# CODEC.net
KiCad netlist of a schematic drawn in Altium Designer
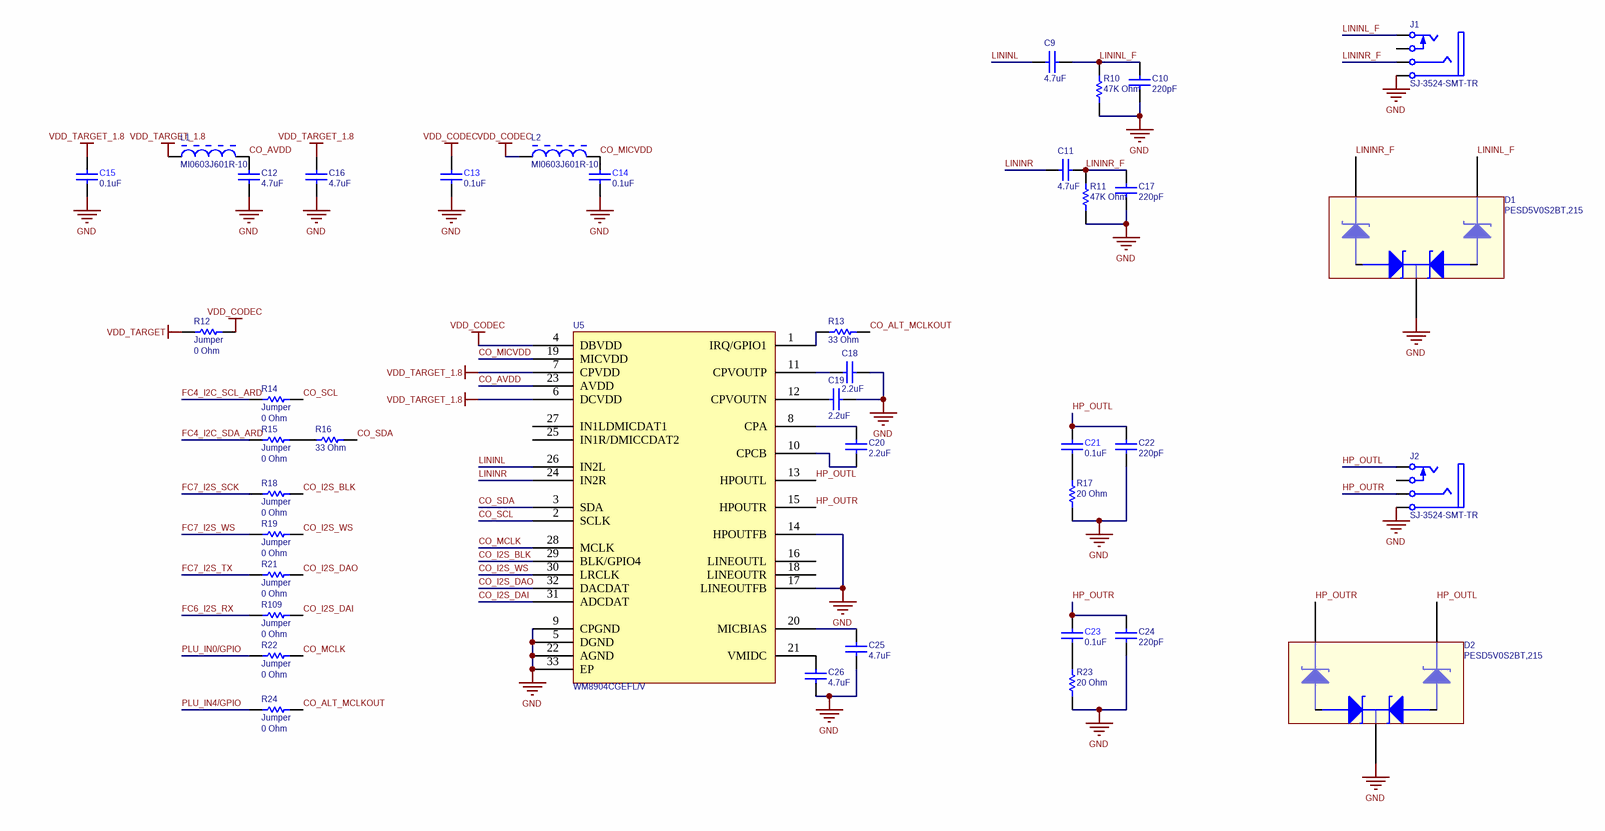
[diagram p0: CODEC.SchDoc]

(export (version "E")
  (design (tool "Eeschema 10.0.6"))
  (components
    (comp (ref "C9")
      (value "4.7uF")
      (footprint "CAPC0603(1608)100_L")
      (description "CAP 4.7uF 10V ±10% 0603 (1608 Metric) Thickness 1mm SMD")
      (fields (field (name "TOLERANCE") "Â±10%") (field (name "Comment") "CAP 4.7uF 10V 0603(1608)"))
      (libsource (lib "Altium Content Vault") (part "CMP-1035-02785-1"))
    )
    (comp (ref "C10")
      (value "220pF")
      (footprint "CAPC0402(1005)60_L")
      (description "CAP 220pF 50V ±1% 0402 (1005 Metric) Thickness 0.6mm SMD")
      (fields (field (name "TOLERANCE") "Â±1%") (field (name "Comment") "CAP 220pF 50V 0402(1005)"))
      (libsource (lib "Altium Content Vault") (part "CMP-1034-01367-1"))
    )
    (comp (ref "C11")
      (value "4.7uF")
      (footprint "CAPC0603(1608)100_L")
      (description "CAP 4.7uF 10V ±10% 0603 (1608 Metric) Thickness 1mm SMD")
      (fields (field (name "TOLERANCE") "Â±10%") (field (name "Comment") "CAP 4.7uF 10V 0603(1608)"))
      (libsource (lib "Altium Content Vault") (part "CMP-1035-02785-1"))
    )
    (comp (ref "C12")
      (value "4.7uF")
      (footprint "CAPC0603(1608)100_L")
      (description "CAP 4.7uF 10V ±10% 0603 (1608 Metric) Thickness 1mm SMD")
      (fields (field (name "TOLERANCE") "Â±10%") (field (name "Comment") "CAP 4.7uF 10V 0603(1608)"))
      (libsource (lib "Altium Content Vault") (part "CMP-1035-02785-1"))
    )
    (comp (ref "C13")
      (value "0.1uF")
      (footprint "CAPC1005")
      (description "Capacitor, Yageo, Ceramic, 0.1uF 10% 16V 0402 (1005) X7R")
      (fields
        (field (name "TOLERANCE") "10 %")
        (field (name "Comment") "CC0402KRX7R7BB104")
        (field (name "PUBLISHER") "Altium")
      )
      (libsource (lib "Altium Content Vault") (part "CMP-0001-00074-1"))
    )
    (comp (ref "C14")
      (value "0.1uF")
      (footprint "CAPC1005")
      (description "Capacitor, Yageo, Ceramic, 0.1uF 10% 16V 0402 (1005) X7R")
      (fields
        (field (name "TOLERANCE") "10 %")
        (field (name "Comment") "CC0402KRX7R7BB104")
        (field (name "PUBLISHER") "Altium")
      )
      (libsource (lib "Altium Content Vault") (part "CMP-0001-00074-1"))
    )
    (comp (ref "C15")
      (value "0.1uF")
      (footprint "CAPC1005")
      (description "Capacitor, Yageo, Ceramic, 0.1uF 10% 16V 0402 (1005) X7R")
      (fields
        (field (name "TOLERANCE") "10 %")
        (field (name "Comment") "CC0402KRX7R7BB104")
        (field (name "PUBLISHER") "Altium")
      )
      (libsource (lib "Altium Content Vault") (part "CMP-0001-00074-1"))
    )
    (comp (ref "C16")
      (value "4.7uF")
      (footprint "CAPC0603(1608)100_L")
      (description "CAP 4.7uF 10V ±10% 0603 (1608 Metric) Thickness 1mm SMD")
      (fields (field (name "TOLERANCE") "Â±10%") (field (name "Comment") "CAP 4.7uF 10V 0603(1608)"))
      (libsource (lib "Altium Content Vault") (part "CMP-1035-02785-1"))
    )
    (comp (ref "C17")
      (value "220pF")
      (footprint "CAPC0402(1005)60_L")
      (description "CAP 220pF 50V ±1% 0402 (1005 Metric) Thickness 0.6mm SMD")
      (fields (field (name "TOLERANCE") "Â±1%") (field (name "Comment") "CAP 220pF 50V 0402(1005)"))
      (libsource (lib "Altium Content Vault") (part "CMP-1034-01367-1"))
    )
    (comp (ref "C18")
      (value "2.2uF")
      (footprint "CAPC0402(1005)60_L")
      (description "CAP 2.2uF 10V ±10% 0402 (1005 Metric) Thickness 0.6mm SMD")
      (fields (field (name "TOLERANCE") "Â±10%") (field (name "Comment") "CAP 2.2uF 10V 0402(1005)"))
      (libsource (lib "Altium Content Vault") (part "CMP-1034-02127-1"))
    )
    (comp (ref "C19")
      (value "2.2uF")
      (footprint "CAPC0402(1005)60_L")
      (description "CAP 2.2uF 10V ±10% 0402 (1005 Metric) Thickness 0.6mm SMD")
      (fields (field (name "TOLERANCE") "Â±10%") (field (name "Comment") "CAP 2.2uF 10V 0402(1005)"))
      (libsource (lib "Altium Content Vault") (part "CMP-1034-02127-1"))
    )
    (comp (ref "C20")
      (value "2.2uF")
      (footprint "CAPC0402(1005)60_L")
      (description "CAP 2.2uF 10V ±10% 0402 (1005 Metric) Thickness 0.6mm SMD")
      (fields (field (name "TOLERANCE") "Â±10%") (field (name "Comment") "CAP 2.2uF 10V 0402(1005)"))
      (libsource (lib "Altium Content Vault") (part "CMP-1034-02127-1"))
    )
    (comp (ref "C21")
      (value "0.1uF")
      (footprint "CAPC1005")
      (description "Capacitor, Yageo, Ceramic, 0.1uF 10% 16V 0402 (1005) X7R")
      (fields
        (field (name "TOLERANCE") "10 %")
        (field (name "Comment") "CC0402KRX7R7BB104")
        (field (name "PUBLISHER") "Altium")
      )
      (libsource (lib "Altium Content Vault") (part "CMP-0001-00074-1"))
    )
    (comp (ref "C22")
      (value "220pF")
      (footprint "CAPC0402(1005)60_L")
      (description "CAP 220pF 50V ±1% 0402 (1005 Metric) Thickness 0.6mm SMD")
      (fields (field (name "TOLERANCE") "Â±1%") (field (name "Comment") "CAP 220pF 50V 0402(1005)"))
      (libsource (lib "Altium Content Vault") (part "CMP-1034-01367-1"))
    )
    (comp (ref "C23")
      (value "0.1uF")
      (footprint "CAPC1005")
      (description "Capacitor, Yageo, Ceramic, 0.1uF 10% 16V 0402 (1005) X7R")
      (fields
        (field (name "TOLERANCE") "10 %")
        (field (name "Comment") "CC0402KRX7R7BB104")
        (field (name "PUBLISHER") "Altium")
      )
      (libsource (lib "Altium Content Vault") (part "CMP-0001-00074-1"))
    )
    (comp (ref "C24")
      (value "220pF")
      (footprint "CAPC0402(1005)60_L")
      (description "CAP 220pF 50V ±1% 0402 (1005 Metric) Thickness 0.6mm SMD")
      (fields (field (name "TOLERANCE") "Â±1%") (field (name "Comment") "CAP 220pF 50V 0402(1005)"))
      (libsource (lib "Altium Content Vault") (part "CMP-1034-01367-1"))
    )
    (comp (ref "C25")
      (value "4.7uF")
      (footprint "CAPC0603(1608)100_L")
      (description "CAP 4.7uF 10V ±10% 0603 (1608 Metric) Thickness 1mm SMD")
      (fields (field (name "TOLERANCE") "Â±10%") (field (name "Comment") "CAP 4.7uF 10V 0603(1608)"))
      (libsource (lib "Altium Content Vault") (part "CMP-1035-02785-1"))
    )
    (comp (ref "C26")
      (value "4.7uF")
      (footprint "CAPC0603(1608)100_L")
      (description "CAP 4.7uF 10V ±10% 0603 (1608 Metric) Thickness 1mm SMD")
      (fields (field (name "TOLERANCE") "Â±10%") (field (name "Comment") "CAP 4.7uF 10V 0603(1608)"))
      (libsource (lib "Altium Content Vault") (part "CMP-1035-02785-1"))
    )
    (comp (ref "D1")
      (value "PESD5V0S2BT,215")
      (footprint "SOT23-3")
      (description "TVS DIODE 5V 14V SOT23")
      (fields
        (field (name "MANUFACTURER") "Nexperia USA Inc.")
        (field (name "CREATED BY") "eteofilo")
        (field (name "MODIFIED BY") "*")
      )
      (libsource (lib "TVS - Diodes") (part "PESD5V0S2BT,215"))
    )
    (comp (ref "D2")
      (value "PESD5V0S2BT,215")
      (footprint "SOT23-3")
      (description "TVS DIODE 5V 14V SOT23")
      (fields
        (field (name "MANUFACTURER") "Nexperia USA Inc.")
        (field (name "CREATED BY") "eteofilo")
        (field (name "MODIFIED BY") "*")
      )
      (libsource (lib "TVS - Diodes") (part "PESD5V0S2BT,215"))
    )
    (comp (ref "J1")
      (value "SJ-3524-SMT-TR")
      (footprint "SJ-3524-SMT-TR")
      (description "CONN AUDIO JACK 3.5MM STEREO SMD")
      (fields
        (field (name "MANUFACTURER") "CUI Inc")
        (field (name "CREATED BY") "gmoreno")
        (field (name "MODIFIED BY") "*")
      )
      (libsource (lib "Barrel - Audio Connectors") (part "SJ-3524-SMT-TR"))
    )
    (comp (ref "J2")
      (value "SJ-3524-SMT-TR")
      (footprint "SJ-3524-SMT-TR")
      (description "CONN AUDIO JACK 3.5MM STEREO SMD")
      (fields
        (field (name "MANUFACTURER") "CUI Inc")
        (field (name "CREATED BY") "gmoreno")
        (field (name "MODIFIED BY") "*")
      )
      (libsource (lib "Barrel - Audio Connectors") (part "SJ-3524-SMT-TR"))
    )
    (comp (ref "L1")
      (value "MI0603J601R-10")
      (footprint "LIRD-MI0603J601R-10_V")
      (description "Ferrite Bead, 600 Ohm, 1 A, -40 to 125 degC, 2-Pin SMD, RoHS, Tape and Reel")
      (fields (field (name "MANUFACTURER") "Laird"))
      (libsource (lib "Altium Content Vault") (part "IND-FB-2"))
    )
    (comp (ref "L2")
      (value "MI0603J601R-10")
      (footprint "LIRD-MI0603J601R-10_V")
      (description "Ferrite Bead, 600 Ohm, 1 A, -40 to 125 degC, 2-Pin SMD, RoHS, Tape and Reel")
      (fields (field (name "MANUFACTURER") "Laird"))
      (libsource (lib "Altium Content Vault") (part "IND-FB-2"))
    )
    (comp (ref "R10")
      (value "47K Ohm")
      (footprint "RESC0402(1005)_L")
      (description "47K 0.063W 1% 0402 (1005 Metric)  SMD")
      (fields (field (name "POWER") "0.063 W") (field (name "TOLERANCE") "1 %"))
      (libsource (lib "Altium Content Vault") (part "CMP-1011-00699-1"))
    )
    (comp (ref "R11")
      (value "47K Ohm")
      (footprint "RESC0402(1005)_L")
      (description "47K 0.063W 1% 0402 (1005 Metric)  SMD")
      (fields (field (name "POWER") "0.063 W") (field (name "TOLERANCE") "1 %"))
      (libsource (lib "Altium Content Vault") (part "CMP-1011-00699-1"))
    )
    (comp (ref "R12")
      (value "Jumper")
      (footprint "RESC0402(1005)_L")
      (description "Jumper 0402 (1005 Metric)")
      (fields (field (name "TOLERANCE") "None") (field (name "ALTIUM_VALUE") "0 Ohm"))
      (libsource (lib "Altium Content Vault") (part "CMP-1011-00001-1"))
    )
    (comp (ref "R13")
      (value "33 Ohm")
      (footprint "RESC0402(1005)_L")
      (description "33R 0.063W 1% 0402 (1005 Metric)  SMD")
      (fields (field (name "TOLERANCE") "1 %") (field (name "POWER") "0.063 W"))
      (libsource (lib "Altium Content Vault") (part "CMP-1011-00341-1"))
    )
    (comp (ref "R14")
      (value "Jumper")
      (footprint "RESC0402(1005)_L")
      (description "Jumper 0402 (1005 Metric)")
      (fields (field (name "TOLERANCE") "None") (field (name "ALTIUM_VALUE") "0 Ohm"))
      (libsource (lib "Altium Content Vault") (part "CMP-1011-00001-1"))
    )
    (comp (ref "R15")
      (value "Jumper")
      (footprint "RESC0402(1005)_L")
      (description "Jumper 0402 (1005 Metric)")
      (fields (field (name "TOLERANCE") "None") (field (name "ALTIUM_VALUE") "0 Ohm"))
      (libsource (lib "Altium Content Vault") (part "CMP-1011-00001-1"))
    )
    (comp (ref "R16")
      (value "33 Ohm")
      (footprint "RESC0402(1005)_L")
      (description "33R 0.063W 1% 0402 (1005 Metric)  SMD")
      (fields (field (name "TOLERANCE") "1 %") (field (name "POWER") "0.063 W"))
      (libsource (lib "Altium Content Vault") (part "CMP-1011-00341-1"))
    )
    (comp (ref "R17")
      (value "20 Ohm")
      (footprint "RESC0402(1005)_L")
      (description "20R 0.063W 1% 0402 (1005 Metric)  SMD")
      (fields (field (name "POWER") "0.063 W") (field (name "TOLERANCE") "1 %"))
      (libsource (lib "Altium Content Vault") (part "CMP-1011-00316-1"))
    )
    (comp (ref "R18")
      (value "Jumper")
      (footprint "RESC0402(1005)_L")
      (description "Jumper 0402 (1005 Metric)")
      (fields (field (name "TOLERANCE") "None") (field (name "ALTIUM_VALUE") "0 Ohm"))
      (libsource (lib "Altium Content Vault") (part "CMP-1011-00001-1"))
    )
    (comp (ref "R19")
      (value "Jumper")
      (footprint "RESC0402(1005)_L")
      (description "Jumper 0402 (1005 Metric)")
      (fields (field (name "TOLERANCE") "None") (field (name "ALTIUM_VALUE") "0 Ohm"))
      (libsource (lib "Altium Content Vault") (part "CMP-1011-00001-1"))
    )
    (comp (ref "R21")
      (value "Jumper")
      (footprint "RESC0402(1005)_L")
      (description "Jumper 0402 (1005 Metric)")
      (fields (field (name "TOLERANCE") "None") (field (name "ALTIUM_VALUE") "0 Ohm"))
      (libsource (lib "Altium Content Vault") (part "CMP-1011-00001-1"))
    )
    (comp (ref "R22")
      (value "Jumper")
      (footprint "RESC0402(1005)_L")
      (description "Jumper 0402 (1005 Metric)")
      (fields (field (name "TOLERANCE") "None") (field (name "ALTIUM_VALUE") "0 Ohm"))
      (libsource (lib "Altium Content Vault") (part "CMP-1011-00001-1"))
    )
    (comp (ref "R23")
      (value "20 Ohm")
      (footprint "RESC0402(1005)_L")
      (description "20R 0.063W 1% 0402 (1005 Metric)  SMD")
      (fields (field (name "POWER") "0.063 W") (field (name "TOLERANCE") "1 %"))
      (libsource (lib "Altium Content Vault") (part "CMP-1011-00316-1"))
    )
    (comp (ref "R24")
      (value "Jumper")
      (footprint "RESC0402(1005)_L")
      (description "Jumper 0402 (1005 Metric)")
      (fields (field (name "TOLERANCE") "None") (field (name "ALTIUM_VALUE") "0 Ohm"))
      (libsource (lib "Altium Content Vault") (part "CMP-1011-00001-1"))
    )
    (comp (ref "R109")
      (value "Jumper")
      (footprint "RESC0402(1005)_L")
      (description "Jumper 0402 (1005 Metric)")
      (fields (field (name "TOLERANCE") "None") (field (name "ALTIUM_VALUE") "0 Ohm"))
      (libsource (lib "Altium Content Vault") (part "CMP-1011-00001-1"))
    )
    (comp (ref "U5")
      (value "WM8904CGEFL/V")
      (footprint "QFN-32 4x4x0.75")
      (description "IC CODEC STEREO ULP 32QFN")
      (fields
        (field (name "MANUFACTURER") "Cirrus Logic Inc.")
        (field (name "CREATED BY") "eteofilo")
        (field (name "MODIFIED BY") "*")
      )
      (libsource (lib "Interface - CODECs") (part "WM8904CGEFL/V"))
    )
  )
  (nets
    (net (code "1") (name "/CO_ALT_MCLKOUT") (class "Default")
      (node (ref "R13") (pin "2") (pinfunction "2_2") (pintype "passive"))
      (node (ref "R24") (pin "1") (pinfunction "1_1") (pintype "passive"))
    )
    (net (code "2") (name "/CO_AVDD") (class "Default")
      (node (ref "C12") (pin "2") (pinfunction "2_2") (pintype "passive"))
      (node (ref "L1") (pin "2") (pinfunction "2_2") (pintype "passive"))
      (node (ref "U5") (pin "23") (pinfunction "AVDD_23") (pintype "passive"))
    )
    (net (code "3") (name "/CO_I2S_BLK") (class "Default")
      (node (ref "R18") (pin "1") (pinfunction "1_1") (pintype "passive"))
      (node (ref "U5") (pin "29") (pinfunction "BLK/GPIO4_29") (pintype "passive"))
    )
    (net (code "4") (name "/CO_I2S_DAI") (class "Default")
      (node (ref "R109") (pin "1") (pinfunction "1_1") (pintype "passive"))
      (node (ref "U5") (pin "31") (pinfunction "ADCDAT_31") (pintype "passive"))
    )
    (net (code "5") (name "/CO_I2S_DAO") (class "Default")
      (node (ref "R21") (pin "1") (pinfunction "1_1") (pintype "passive"))
      (node (ref "U5") (pin "32") (pinfunction "DACDAT_32") (pintype "passive"))
    )
    (net (code "6") (name "/CO_I2S_WS") (class "Default")
      (node (ref "R19") (pin "1") (pinfunction "1_1") (pintype "passive"))
      (node (ref "U5") (pin "30") (pinfunction "LRCLK_30") (pintype "passive"))
    )
    (net (code "7") (name "/CO_MCLK") (class "Default")
      (node (ref "R22") (pin "1") (pinfunction "1_1") (pintype "passive"))
      (node (ref "U5") (pin "28") (pinfunction "MCLK_28") (pintype "passive"))
    )
    (net (code "8") (name "/CO_MICVDD") (class "Default")
      (node (ref "C14") (pin "1") (pinfunction "1_1") (pintype "passive"))
      (node (ref "L2") (pin "2") (pinfunction "2_2") (pintype "passive"))
      (node (ref "U5") (pin "19") (pinfunction "MICVDD_19") (pintype "passive"))
    )
    (net (code "9") (name "/CO_SCL") (class "Default")
      (node (ref "R14") (pin "1") (pinfunction "1_1") (pintype "passive"))
      (node (ref "U5") (pin "2") (pinfunction "SCLK_2") (pintype "passive"))
    )
    (net (code "10") (name "/CO_SDA") (class "Default")
      (node (ref "R16") (pin "2") (pinfunction "2_2") (pintype "passive"))
      (node (ref "U5") (pin "3") (pinfunction "SDA_3") (pintype "passive"))
    )
    (net (code "11") (name "/FC4_I2C_SCL_ARD") (class "Default")
      (node (ref "R14") (pin "2") (pinfunction "2_2") (pintype "passive"))
    )
    (net (code "12") (name "/FC4_I2C_SDA_ARD") (class "Default")
      (node (ref "R15") (pin "2") (pinfunction "2_2") (pintype "passive"))
    )
    (net (code "13") (name "/FC6_I2S_RX") (class "Default")
      (node (ref "R109") (pin "2") (pinfunction "2_2") (pintype "passive"))
    )
    (net (code "14") (name "/FC7_I2S_SCK") (class "Default")
      (node (ref "R18") (pin "2") (pinfunction "2_2") (pintype "passive"))
    )
    (net (code "15") (name "/FC7_I2S_TX") (class "Default")
      (node (ref "R21") (pin "2") (pinfunction "2_2") (pintype "passive"))
    )
    (net (code "16") (name "/FC7_I2S_WS") (class "Default")
      (node (ref "R19") (pin "2") (pinfunction "2_2") (pintype "passive"))
    )
    (net (code "17") (name "/HP_OUTL") (class "Default")
      (node (ref "C21") (pin "1") (pinfunction "1_1") (pintype "passive"))
      (node (ref "C22") (pin "2") (pinfunction "2_2") (pintype "passive"))
      (node (ref "D2") (pin "1") (pinfunction "K1_1") (pintype "passive"))
      (node (ref "J2") (pin "2") (pinfunction "Tip_2") (pintype "passive"))
      (node (ref "U5") (pin "13") (pinfunction "HPOUTL_13") (pintype "passive"))
    )
    (net (code "18") (name "/HP_OUTR") (class "Default")
      (node (ref "C23") (pin "1") (pinfunction "1_1") (pintype "passive"))
      (node (ref "C24") (pin "2") (pinfunction "2_2") (pintype "passive"))
      (node (ref "D2") (pin "2") (pinfunction "K2_2") (pintype "passive"))
      (node (ref "J2") (pin "3") (pinfunction "Ring_3") (pintype "passive"))
      (node (ref "U5") (pin "15") (pinfunction "HPOUTR_15") (pintype "passive"))
    )
    (net (code "19") (name "/LININL") (class "Default")
      (node (ref "C9") (pin "2") (pinfunction "2_2") (pintype "passive"))
      (node (ref "U5") (pin "26") (pinfunction "IN2L_26") (pintype "passive"))
    )
    (net (code "20") (name "/LININL_F") (class "Default")
      (node (ref "C10") (pin "2") (pinfunction "2_2") (pintype "passive"))
      (node (ref "C9") (pin "1") (pinfunction "1_1") (pintype "passive"))
      (node (ref "D1") (pin "1") (pinfunction "K1_1") (pintype "passive"))
      (node (ref "J1") (pin "2") (pinfunction "Tip_2") (pintype "passive"))
      (node (ref "R10") (pin "2") (pinfunction "2_2") (pintype "passive"))
    )
    (net (code "21") (name "/LININR") (class "Default")
      (node (ref "C11") (pin "2") (pinfunction "2_2") (pintype "passive"))
      (node (ref "U5") (pin "24") (pinfunction "IN2R_24") (pintype "passive"))
    )
    (net (code "22") (name "/LININR_F") (class "Default")
      (node (ref "C11") (pin "1") (pinfunction "1_1") (pintype "passive"))
      (node (ref "C17") (pin "2") (pinfunction "2_2") (pintype "passive"))
      (node (ref "D1") (pin "2") (pinfunction "K2_2") (pintype "passive"))
      (node (ref "J1") (pin "3") (pinfunction "Ring_3") (pintype "passive"))
      (node (ref "R11") (pin "2") (pinfunction "2_2") (pintype "passive"))
    )
    (net (code "23") (name "/PLU_IN0{slash}GPIO") (class "Default")
      (node (ref "R22") (pin "2") (pinfunction "2_2") (pintype "passive"))
    )
    (net (code "24") (name "/PLU_IN4{slash}GPIO") (class "Default")
      (node (ref "R24") (pin "2") (pinfunction "2_2") (pintype "passive"))
    )
    (net (code "25") (name "GND") (class "Default")
      (node (ref "C10") (pin "1") (pinfunction "1_1") (pintype "passive"))
      (node (ref "C12") (pin "1") (pinfunction "1_1") (pintype "passive"))
      (node (ref "C13") (pin "2") (pinfunction "2_2") (pintype "passive"))
      (node (ref "C14") (pin "2") (pinfunction "2_2") (pintype "passive"))
      (node (ref "C15") (pin "2") (pinfunction "2_2") (pintype "passive"))
      (node (ref "C16") (pin "1") (pinfunction "1_1") (pintype "passive"))
      (node (ref "C17") (pin "1") (pinfunction "1_1") (pintype "passive"))
      (node (ref "C18") (pin "1") (pinfunction "1_1") (pintype "passive"))
      (node (ref "C19") (pin "1") (pinfunction "1_1") (pintype "passive"))
      (node (ref "C22") (pin "1") (pinfunction "1_1") (pintype "passive"))
      (node (ref "C24") (pin "1") (pinfunction "1_1") (pintype "passive"))
      (node (ref "C25") (pin "1") (pinfunction "1_1") (pintype "passive"))
      (node (ref "C26") (pin "1") (pinfunction "1_1") (pintype "passive"))
      (node (ref "D1") (pin "3") (pinfunction "DK_3") (pintype "passive"))
      (node (ref "D2") (pin "3") (pinfunction "DK_3") (pintype "passive"))
      (node (ref "J1") (pin "1") (pinfunction "Sleeve_1") (pintype "power_in"))
      (node (ref "J2") (pin "1") (pinfunction "Sleeve_1") (pintype "power_in"))
      (node (ref "R10") (pin "1") (pinfunction "1_1") (pintype "passive"))
      (node (ref "R11") (pin "1") (pinfunction "1_1") (pintype "passive"))
      (node (ref "R17") (pin "1") (pinfunction "1_1") (pintype "passive"))
      (node (ref "R23") (pin "1") (pinfunction "1_1") (pintype "passive"))
      (node (ref "U5") (pin "14") (pinfunction "HPOUTFB_14") (pintype "passive"))
      (node (ref "U5") (pin "17") (pinfunction "LINEOUTFB_17") (pintype "passive"))
      (node (ref "U5") (pin "22") (pinfunction "AGND_22") (pintype "passive"))
      (node (ref "U5") (pin "33") (pinfunction "EP_33") (pintype "passive"))
      (node (ref "U5") (pin "5") (pinfunction "DGND_5") (pintype "passive"))
      (node (ref "U5") (pin "9") (pinfunction "CPGND_9") (pintype "passive"))
    )
    (net (code "26") (name "Net-(C21-Pad2)") (class "Default")
      (node (ref "C21") (pin "2") (pinfunction "2_2") (pintype "passive"))
      (node (ref "R17") (pin "2") (pinfunction "2_2") (pintype "passive"))
    )
    (net (code "27") (name "Net-(C23-Pad2)") (class "Default")
      (node (ref "C23") (pin "2") (pinfunction "2_2") (pintype "passive"))
      (node (ref "R23") (pin "2") (pinfunction "2_2") (pintype "passive"))
    )
    (net (code "28") (name "Net-(R15-Pad1)") (class "Default")
      (node (ref "R15") (pin "1") (pinfunction "1_1") (pintype "passive"))
      (node (ref "R16") (pin "1") (pinfunction "1_1") (pintype "passive"))
    )
    (net (code "29") (name "Net-(U5-CPA)") (class "Default")
      (node (ref "C20") (pin "2") (pinfunction "2_2") (pintype "passive"))
      (node (ref "U5") (pin "8") (pinfunction "CPA_8") (pintype "passive"))
    )
    (net (code "30") (name "Net-(U5-CPCB)") (class "Default")
      (node (ref "C20") (pin "1") (pinfunction "1_1") (pintype "passive"))
      (node (ref "U5") (pin "10") (pinfunction "CPCB_10") (pintype "passive"))
    )
    (net (code "31") (name "Net-(U5-CPVOUTN)") (class "Default")
      (node (ref "C19") (pin "2") (pinfunction "2_2") (pintype "passive"))
      (node (ref "U5") (pin "12") (pinfunction "CPVOUTN_12") (pintype "passive"))
    )
    (net (code "32") (name "Net-(U5-CPVOUTP)") (class "Default")
      (node (ref "C18") (pin "2") (pinfunction "2_2") (pintype "passive"))
      (node (ref "U5") (pin "11") (pinfunction "CPVOUTP_11") (pintype "passive"))
    )
    (net (code "33") (name "Net-(U5-IRQ{slash}GPIO1)") (class "Default")
      (node (ref "R13") (pin "1") (pinfunction "1_1") (pintype "passive"))
      (node (ref "U5") (pin "1") (pinfunction "IRQ/GPIO1_1") (pintype "passive"))
    )
    (net (code "34") (name "Net-(U5-MICBIAS)") (class "Default")
      (node (ref "C25") (pin "2") (pinfunction "2_2") (pintype "passive"))
      (node (ref "U5") (pin "20") (pinfunction "MICBIAS_20") (pintype "passive"))
    )
    (net (code "35") (name "Net-(U5-VMIDC)") (class "Default")
      (node (ref "C26") (pin "2") (pinfunction "2_2") (pintype "passive"))
      (node (ref "U5") (pin "21") (pinfunction "VMIDC_21") (pintype "passive"))
    )
    (net (code "36") (name "VDD_CODEC") (class "Default")
      (node (ref "C13") (pin "1") (pinfunction "1_1") (pintype "passive"))
      (node (ref "L2") (pin "1") (pinfunction "1_1") (pintype "passive"))
      (node (ref "R12") (pin "1") (pinfunction "1_1") (pintype "passive"))
      (node (ref "U5") (pin "4") (pinfunction "DBVDD_4") (pintype "passive"))
    )
    (net (code "37") (name "VDD_TARGET") (class "Default")
      (node (ref "R12") (pin "2") (pinfunction "2_2") (pintype "passive"))
    )
    (net (code "38") (name "VDD_TARGET_1.8") (class "Default")
      (node (ref "C15") (pin "1") (pinfunction "1_1") (pintype "passive"))
      (node (ref "C16") (pin "2") (pinfunction "2_2") (pintype "passive"))
      (node (ref "L1") (pin "1") (pinfunction "1_1") (pintype "passive"))
      (node (ref "U5") (pin "6") (pinfunction "DCVDD_6") (pintype "passive"))
      (node (ref "U5") (pin "7") (pinfunction "CPVDD_7") (pintype "passive"))
    )
    (net (code "39") (name "unconnected-(J1-Pad0)") (class "Default")
      (node (ref "J1") (pin "0") (pinfunction "0_0") (pintype "passive"))
    )
    (net (code "40") (name "unconnected-(J1-Tip_Switch-Pad4)") (class "Default")
      (node (ref "J1") (pin "4") (pinfunction "Tip_Switch_4") (pintype "passive"))
    )
    (net (code "41") (name "unconnected-(J2-Pad0)") (class "Default")
      (node (ref "J2") (pin "0") (pinfunction "0_0") (pintype "passive"))
    )
    (net (code "42") (name "unconnected-(J2-Tip_Switch-Pad4)") (class "Default")
      (node (ref "J2") (pin "4") (pinfunction "Tip_Switch_4") (pintype "passive"))
    )
    (net (code "43") (name "unconnected-(U5-IN1LDMICDAT1-Pad27)") (class "Default")
      (node (ref "U5") (pin "27") (pinfunction "IN1LDMICDAT1_27") (pintype "passive"))
    )
    (net (code "44") (name "unconnected-(U5-IN1R{slash}DMICCDAT2-Pad25)") (class "Default")
      (node (ref "U5") (pin "25") (pinfunction "IN1R/DMICCDAT2_25") (pintype "passive"))
    )
    (net (code "45") (name "unconnected-(U5-LINEOUTL-Pad16)") (class "Default")
      (node (ref "U5") (pin "16") (pinfunction "LINEOUTL_16") (pintype "passive"))
    )
    (net (code "46") (name "unconnected-(U5-LINEOUTR-Pad18)") (class "Default")
      (node (ref "U5") (pin "18") (pinfunction "LINEOUTR_18") (pintype "passive"))
    )
  )
)
